# MAX16998A_Watchdog_Circuit.net
KiCad netlist of a schematic drawn in Altium Designer
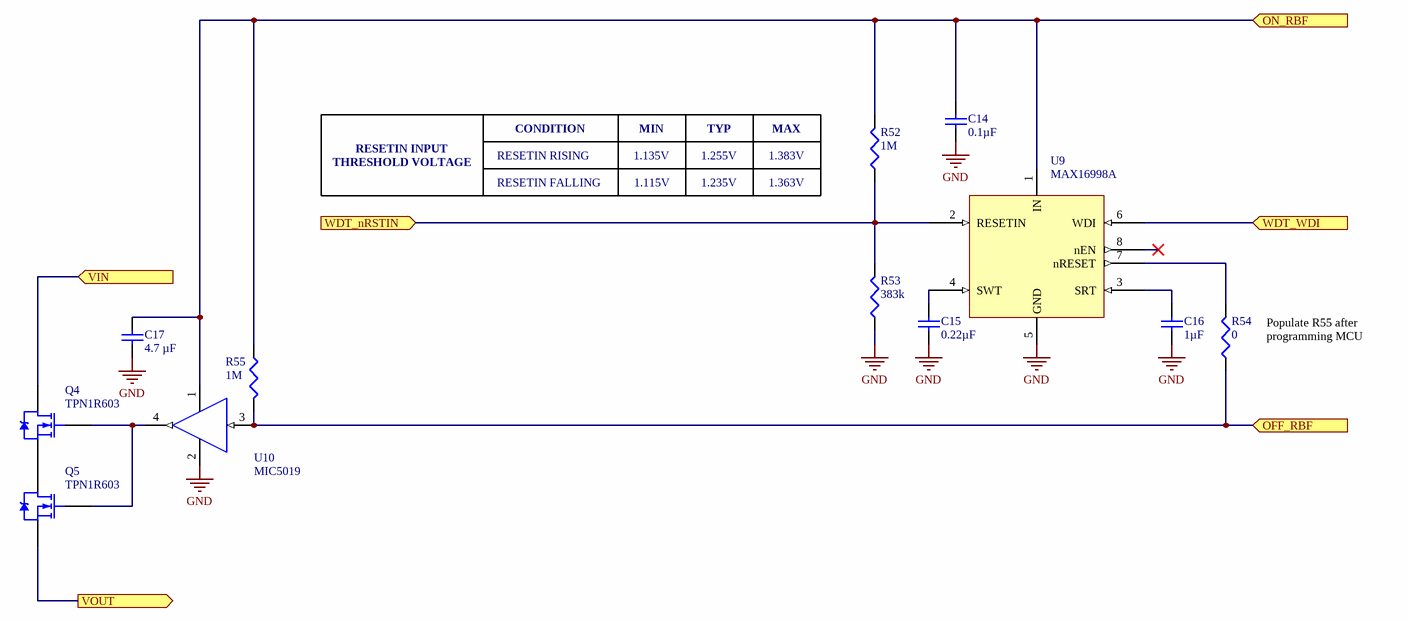
[diagram p0: MAX16998A Watchdog Circuit.SchDoc]

(export (version "E")
  (design (tool "Eeschema 10.0.6"))
  (components
    (comp (ref "C14")
      (value "0.1µF")
      (footprint "TDK-CGA2B")
      (description "CAP CER 0.1UF 50V X7R 0402")
      (fields
        (field (name "PART NUMBER") "PC-TDK-02259")
        (field (name "MANUFACTURER PART NUMBER") "CGA2B3X7R1H104K050BB")
        (field (name "PUBLISHER") "AlbertaSat")
      )
      (libsource (lib "Database") (part "Cap"))
    )
    (comp (ref "C15")
      (value "0.22µF")
      (footprint "TDK-CGA3E")
      (description "CAP CER 0.22UF 50V X7R 0603")
      (fields
        (field (name "PART NUMBER") "PC-TDK-02393")
        (field (name "MANUFACTURER PART NUMBER") "CGA3E3X7R1H224K080AB")
        (field (name "PUBLISHER") "AlbertaSat")
      )
      (libsource (lib "Database") (part "Cap"))
    )
    (comp (ref "C16")
      (value "1µF")
      (footprint "TY-0603A")
      (description "CAP CER 1UF 50V X7R 0603")
      (fields
        (field (name "PART NUMBER") "PC-TY-00404")
        (field (name "MANUFACTURER PART NUMBER") "UMK107AB7105KA-T")
        (field (name "PUBLISHER") "AlbertaSat")
      )
      (libsource (lib "Database") (part "Cap"))
    )
    (comp (ref "C17")
      (value "4.7 µF")
      (footprint "MUR-GRM188")
      (description "CAP CER 4.7UF 16V X7R 0603")
      (fields
        (field (name "PART NUMBER") "10165")
        (field (name "MANUFACTURER PART NUMBER") "GRM188Z71C475KE21D")
        (field (name "PUBLISHER") "Altium Limited")
      )
      (libsource (lib "Database") (part "Cap"))
    )
    (comp (ref "Q4")
      (value "TPN1R603")
      (footprint "TOSH-S-3X1S")
      (description "X35 PB-F POWER MOSFET TRANSISTOR")
      (fields
        (field (name "PART NUMBER") "PU-TOSH-00002")
        (field (name "MANUFACTURER PART NUMBER") "TPN1R603PL,L1Q")
        (field (name "PUBLISHER") "AlbertaSat")
      )
      (libsource (lib "Database") (part "TPN1R603PL,L1Q"))
    )
    (comp (ref "Q5")
      (value "TPN1R603")
      (footprint "TOSH-S-3X1S")
      (description "X35 PB-F POWER MOSFET TRANSISTOR")
      (fields
        (field (name "PART NUMBER") "PU-TOSH-00002")
        (field (name "MANUFACTURER PART NUMBER") "TPN1R603PL,L1Q")
        (field (name "PUBLISHER") "AlbertaSat")
      )
      (libsource (lib "Database") (part "TPN1R603PL,L1Q"))
    )
    (comp (ref "R52")
      (value "1M")
      (footprint "PANA-ERJ2R")
      (description "RES SMD 1M OHM 1% 1/10W 0402")
      (fields
        (field (name "PART NUMBER") "19704")
        (field (name "MANUFACTURER PART NUMBER") "ERJ-2RKF1004X")
        (field (name "PUBLISHER") "Altium Limited")
      )
      (libsource (lib "Database") (part "Res3"))
    )
    (comp (ref "R53")
      (value "383k")
      (footprint "PANA-ERJ2R")
      (description "RES SMD 383K OHM 1% 1/10W 0402")
      (fields
        (field (name "PART NUMBER") "19322")
        (field (name "MANUFACTURER PART NUMBER") "ERJ-2RKF3833X")
        (field (name "PUBLISHER") "Altium Limited")
      )
      (libsource (lib "Database") (part "Res3"))
    )
    (comp (ref "R54")
      (value "0")
      (footprint "PANA-ERJ2G")
      (description "RES SMD 0.0OHM JUMPER 1/10W 0402")
      (fields (field (name "PART NUMBER") "13127") (field (name "MANUFACTURER PART NUMBER") "ERJ-2GE0R00X"))
      (libsource (lib "Database") (part "Jumper3"))
    )
    (comp (ref "R55")
      (value "1M")
      (footprint "PANA-ERJ2R")
      (description "RES SMD 1M OHM 1% 1/10W 0402")
      (fields
        (field (name "PART NUMBER") "19704")
        (field (name "MANUFACTURER PART NUMBER") "ERJ-2RKF1004X")
        (field (name "PUBLISHER") "Altium Limited")
      )
      (libsource (lib "Database") (part "Res3"))
    )
    (comp (ref "U9")
      (value "MAX16998A")
      (footprint "MAX-21-0036")
      (description "IC TIMER WATCHDOG 8UMAX")
      (fields
        (field (name "PART NUMBER") "PU-MAX-00002")
        (field (name "MANUFACTURER PART NUMBER") "MAX16998AAUA/V+")
        (field (name "PUBLISHER") "AlbertaSat")
      )
      (libsource (lib "Database") (part "MAX16998A"))
    )
    (comp (ref "U10")
      (value "MIC5019")
      (footprint "MCP-MIC5019")
      (description "IC GATE DRVR HIGH-SIDE 4TQFN")
      (fields
        (field (name "PART NUMBER") "PU-MCP-00008")
        (field (name "MANUFACTURER PART NUMBER") "MIC5019YFT-TR")
        (field (name "PUBLISHER") "AlbertaSat")
      )
      (libsource (lib "Database") (part "MIC5019YFT-TR"))
    )
  )
  (nets
    (net (code "1") (name "/OFF_RBF") (class "Default")
      (node (ref "R54") (pin "1") (pinfunction "1_1") (pintype "passive"))
      (node (ref "R55") (pin "1") (pinfunction "1_1") (pintype "passive"))
      (node (ref "U10") (pin "3") (pinfunction "IN_3") (pintype "input"))
    )
    (net (code "2") (name "/ON_RBF") (class "Default")
      (node (ref "C14") (pin "1") (pinfunction "1_1") (pintype "passive"))
      (node (ref "C17") (pin "2") (pinfunction "2_2") (pintype "passive"))
      (node (ref "R52") (pin "2") (pinfunction "2_2") (pintype "passive"))
      (node (ref "R55") (pin "2") (pinfunction "2_2") (pintype "passive"))
      (node (ref "U10") (pin "1") (pinfunction "VDD_1") (pintype "power_in"))
      (node (ref "U9") (pin "1") (pinfunction "IN_1") (pintype "power_in"))
    )
    (net (code "3") (name "/VIN") (class "Default")
      (node (ref "Q4") (pin "2") (pinfunction "D_2") (pintype "passive"))
    )
    (net (code "4") (name "/VOUT") (class "Default")
      (node (ref "Q5") (pin "3") (pinfunction "S_3") (pintype "passive"))
    )
    (net (code "5") (name "/WDT_WDI") (class "Default")
      (node (ref "U9") (pin "6") (pinfunction "WDI_6") (pintype "input"))
    )
    (net (code "6") (name "/WDT_nRSTIN") (class "Default")
      (node (ref "R52") (pin "1") (pinfunction "1_1") (pintype "passive"))
      (node (ref "R53") (pin "2") (pinfunction "2_2") (pintype "passive"))
      (node (ref "U9") (pin "2") (pinfunction "RESETIN_2") (pintype "input"))
    )
    (net (code "7") (name "GND") (class "Default")
      (node (ref "C14") (pin "2") (pinfunction "2_2") (pintype "passive"))
      (node (ref "C15") (pin "1") (pinfunction "1_1") (pintype "passive"))
      (node (ref "C16") (pin "1") (pinfunction "1_1") (pintype "passive"))
      (node (ref "C17") (pin "1") (pinfunction "1_1") (pintype "passive"))
      (node (ref "R53") (pin "1") (pinfunction "1_1") (pintype "passive"))
      (node (ref "U10") (pin "2") (pinfunction "GND_2") (pintype "power_in"))
      (node (ref "U9") (pin "5") (pinfunction "GND_5") (pintype "power_in"))
    )
    (net (code "8") (name "Net-(Q4-G)") (class "Default")
      (node (ref "Q4") (pin "1") (pinfunction "G_1") (pintype "passive"))
      (node (ref "Q5") (pin "1") (pinfunction "G_1") (pintype "passive"))
      (node (ref "U10") (pin "4") (pinfunction "OUT_4") (pintype "output"))
    )
    (net (code "9") (name "Net-(Q4-S)") (class "Default")
      (node (ref "Q4") (pin "3") (pinfunction "S_3") (pintype "passive"))
      (node (ref "Q5") (pin "2") (pinfunction "D_2") (pintype "passive"))
    )
    (net (code "10") (name "Net-(U9-SRT)") (class "Default")
      (node (ref "C16") (pin "2") (pinfunction "2_2") (pintype "passive"))
      (node (ref "U9") (pin "3") (pinfunction "SRT_3") (pintype "input"))
    )
    (net (code "11") (name "Net-(U9-SWT)") (class "Default")
      (node (ref "C15") (pin "2") (pinfunction "2_2") (pintype "passive"))
      (node (ref "U9") (pin "4") (pinfunction "SWT_4") (pintype "input"))
    )
    (net (code "12") (name "Net-(U9-nRESET)") (class "Default")
      (node (ref "R54") (pin "2") (pinfunction "2_2") (pintype "passive"))
      (node (ref "U9") (pin "7") (pinfunction "nRESET_7") (pintype "output"))
    )
    (net (code "13") (name "unconnected-(U9-nEN-Pad8)") (class "Default")
      (node (ref "U9") (pin "8") (pinfunction "nEN_8") (pintype "output+no_connect"))
    )
  )
)
